# SecurityLock.net
KiCad netlist of a schematic drawn in Altium Designer
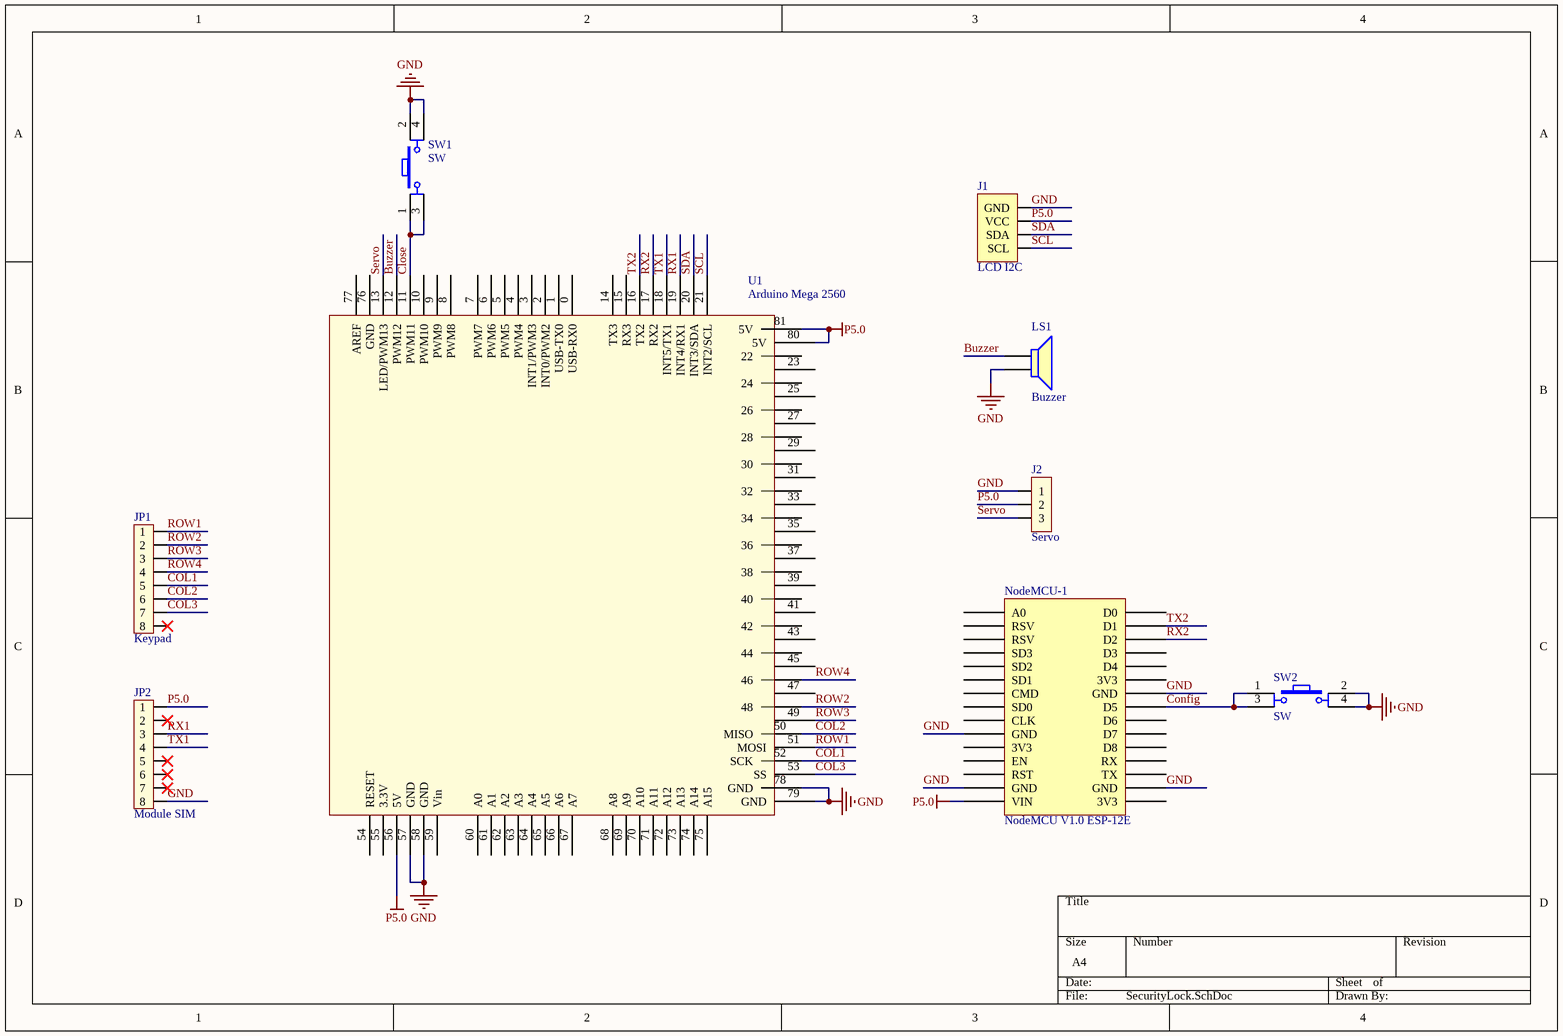
[diagram p0: SecurityLock.SchDoc]

(export (version "E")
  (design (tool "Eeschema 10.0.6"))
  (components
    (comp (ref "J1") (value "LCD I2C") (footprint "LCD16x2_I2C") (libsource (lib "jmctvs") (part "LCD I2C")))
    (comp (ref "J2")
      (value "Servo")
      (footprint "JP3")
      (description "Jumper 3")
      (libsource (lib "jmctvs") (part "JP3"))
    )
    (comp (ref "JP1")
      (value "Keypad")
      (footprint "JP8")
      (description "JP8 PIN")
      (libsource (lib "jmctvs") (part "JP8"))
    )
    (comp (ref "JP2")
      (value "Module SIM")
      (footprint "JP8")
      (description "JP8 PIN")
      (libsource (lib "jmctvs") (part "JP8"))
    )
    (comp (ref "LS1")
      (value "Buzzer")
      (footprint "Buzzer")
      (description "Magnetic Transducer Buzzer")
      (fields (field (name "DESIGNED BY") "John MacTavish"))
      (libsource (lib "jmctvs") (part "Buzzer"))
    )
    (comp (ref "NodeMCU-1")
      (value "NodeMCU V1.0 ESP-12E")
      (footprint "jmctvs:NodeMCU V1.0 ESP-12E")
      (description "NodeMCU V1.0 ESP8266 (ESP-12E)")
      (libsource (lib "jmctvs") (part "NodeMCU V1.0 ESP-12E"))
    )
    (comp (ref "SW1")
      (value "SW")
      (footprint "SW4")
      (description "Switch button 4 pin")
      (libsource (lib "jmctvs") (part "SW4"))
    )
    (comp (ref "SW2")
      (value "SW")
      (footprint "SW4")
      (description "Switch button 4 pin")
      (libsource (lib "") (part "SW4_1"))
    )
    (comp (ref "U1")
      (value "Arduino Mega 2560")
      (footprint "Arduino System:Arduino")
      (libsource (lib "jmctvs") (part "Arduino Mega 2560"))
    )
  )
  (nets
    (net (code "1") (name "/Buzzer") (class "Default")
      (node (ref "LS1") (pin "1") (pinfunction "1_1") (pintype "passive"))
      (node (ref "U1") (pin "12") (pinfunction "PWM12_12") (pintype "passive"))
    )
    (net (code "2") (name "/COL1") (class "Default")
      (node (ref "JP1") (pin "5") (pinfunction "5_5") (pintype "passive"))
      (node (ref "U1") (pin "52") (pinfunction "SCK_52") (pintype "passive"))
    )
    (net (code "3") (name "/COL2") (class "Default")
      (node (ref "JP1") (pin "6") (pinfunction "6_6") (pintype "passive"))
      (node (ref "U1") (pin "50") (pinfunction "MISO_50") (pintype "passive"))
    )
    (net (code "4") (name "/COL3") (class "Default")
      (node (ref "JP1") (pin "7") (pinfunction "7_7") (pintype "passive"))
      (node (ref "U1") (pin "53") (pinfunction "SS_53") (pintype "passive"))
    )
    (net (code "5") (name "/Close") (class "Default")
      (node (ref "SW1") (pin "1") (pintype "passive"))
      (node (ref "SW1") (pin "3") (pintype "passive"))
      (node (ref "U1") (pin "11") (pinfunction "PWM11_11") (pintype "passive"))
    )
    (net (code "6") (name "/Config") (class "Default")
      (node (ref "NodeMCU-1") (pin "D5") (pinfunction "D5_D5") (pintype "passive"))
      (node (ref "SW2") (pin "1") (pintype "passive"))
      (node (ref "SW2") (pin "3") (pintype "passive"))
    )
    (net (code "7") (name "/ROW1") (class "Default")
      (node (ref "JP1") (pin "1") (pinfunction "1_1") (pintype "passive"))
      (node (ref "U1") (pin "51") (pinfunction "MOSI_51") (pintype "passive"))
    )
    (net (code "8") (name "/ROW2") (class "Default")
      (node (ref "JP1") (pin "2") (pinfunction "2_2") (pintype "passive"))
      (node (ref "U1") (pin "48") (pinfunction "48_48") (pintype "passive"))
    )
    (net (code "9") (name "/ROW3") (class "Default")
      (node (ref "JP1") (pin "3") (pinfunction "3_3") (pintype "passive"))
      (node (ref "U1") (pin "49") (pinfunction "49_49") (pintype "passive"))
    )
    (net (code "10") (name "/ROW4") (class "Default")
      (node (ref "JP1") (pin "4") (pinfunction "4_4") (pintype "passive"))
      (node (ref "U1") (pin "46") (pinfunction "46_46") (pintype "passive"))
    )
    (net (code "11") (name "/RX1") (class "Default")
      (node (ref "JP2") (pin "3") (pinfunction "3_3") (pintype "passive"))
      (node (ref "U1") (pin "19") (pinfunction "INT4/RX1_19") (pintype "passive"))
    )
    (net (code "12") (name "/RX2") (class "Default")
      (node (ref "NodeMCU-1") (pin "D2") (pinfunction "D2_D2") (pintype "passive"))
      (node (ref "U1") (pin "17") (pinfunction "RX2_17") (pintype "passive"))
    )
    (net (code "13") (name "/SCL") (class "Default")
      (node (ref "J1") (pin "4") (pinfunction "SCL_4") (pintype "passive"))
      (node (ref "U1") (pin "21") (pinfunction "INT2/SCL_21") (pintype "passive"))
    )
    (net (code "14") (name "/SDA") (class "Default")
      (node (ref "J1") (pin "3") (pinfunction "SDA_3") (pintype "passive"))
      (node (ref "U1") (pin "20") (pinfunction "INT3/SDA_20") (pintype "passive"))
    )
    (net (code "15") (name "/Servo") (class "Default")
      (node (ref "J2") (pin "3") (pinfunction "3_3") (pintype "passive"))
      (node (ref "U1") (pin "13") (pinfunction "LED/PWM13_13") (pintype "passive"))
    )
    (net (code "16") (name "/TX1") (class "Default")
      (node (ref "JP2") (pin "4") (pinfunction "4_4") (pintype "passive"))
      (node (ref "U1") (pin "18") (pinfunction "INT5/TX1_18") (pintype "passive"))
    )
    (net (code "17") (name "/TX2") (class "Default")
      (node (ref "NodeMCU-1") (pin "D1") (pinfunction "D1_D1") (pintype "passive"))
      (node (ref "U1") (pin "16") (pinfunction "TX2_16") (pintype "passive"))
    )
    (net (code "18") (name "GND") (class "Default")
      (node (ref "J1") (pin "1") (pinfunction "GND_1") (pintype "passive"))
      (node (ref "J2") (pin "1") (pinfunction "1_1") (pintype "passive"))
      (node (ref "JP2") (pin "8") (pinfunction "8_8") (pintype "passive"))
      (node (ref "LS1") (pin "2") (pinfunction "2_2") (pintype "passive"))
      (node (ref "NodeMCU-1") (pin "GND") (pinfunction "GND_GND") (pintype "passive"))
      (node (ref "SW1") (pin "2") (pintype "passive"))
      (node (ref "SW1") (pin "4") (pintype "passive"))
      (node (ref "SW2") (pin "2") (pintype "passive"))
      (node (ref "SW2") (pin "4") (pintype "passive"))
      (node (ref "U1") (pin "57") (pinfunction "GND_57") (pintype "passive"))
      (node (ref "U1") (pin "58") (pinfunction "GND_58") (pintype "passive"))
      (node (ref "U1") (pin "78") (pinfunction "GND_78") (pintype "passive"))
      (node (ref "U1") (pin "79") (pinfunction "GND_79") (pintype "passive"))
    )
    (net (code "19") (name "P5.0") (class "Default")
      (node (ref "J1") (pin "2") (pinfunction "VCC_2") (pintype "passive"))
      (node (ref "J2") (pin "2") (pinfunction "2_2") (pintype "passive"))
      (node (ref "JP2") (pin "1") (pinfunction "1_1") (pintype "passive"))
      (node (ref "NodeMCU-1") (pin "VIN") (pinfunction "VIN_VIN") (pintype "passive"))
      (node (ref "U1") (pin "56") (pinfunction "5V_56") (pintype "passive"))
      (node (ref "U1") (pin "80") (pinfunction "5V_80") (pintype "passive"))
      (node (ref "U1") (pin "81") (pinfunction "5V_81") (pintype "passive"))
    )
    (net (code "20") (name "unconnected-(JP1-Pad8)") (class "Default")
      (node (ref "JP1") (pin "8") (pinfunction "8_8") (pintype "passive+no_connect"))
    )
    (net (code "21") (name "unconnected-(JP2-Pad2)") (class "Default")
      (node (ref "JP2") (pin "2") (pinfunction "2_2") (pintype "passive+no_connect"))
    )
    (net (code "22") (name "unconnected-(JP2-Pad5)") (class "Default")
      (node (ref "JP2") (pin "5") (pinfunction "5_5") (pintype "passive+no_connect"))
    )
    (net (code "23") (name "unconnected-(JP2-Pad6)") (class "Default")
      (node (ref "JP2") (pin "6") (pinfunction "6_6") (pintype "passive+no_connect"))
    )
    (net (code "24") (name "unconnected-(JP2-Pad7)") (class "Default")
      (node (ref "JP2") (pin "7") (pinfunction "7_7") (pintype "passive+no_connect"))
    )
    (net (code "25") (name "unconnected-(NodeMCU-1-Pad3V3)") (class "Default")
      (node (ref "NodeMCU-1") (pin "3V3") (pinfunction "3V3_3V3") (pintype "passive"))
    )
    (net (code "26") (name "unconnected-(NodeMCU-1-Pad3V3)_1") (class "Default")
      (node (ref "NodeMCU-1") (pin "3V3") (pinfunction "3V3_3V3") (pintype "passive"))
    )
    (net (code "27") (name "unconnected-(NodeMCU-1-Pad3V3)_2") (class "Default")
      (node (ref "NodeMCU-1") (pin "3V3") (pinfunction "3V3_3V3") (pintype "passive"))
    )
    (net (code "28") (name "unconnected-(NodeMCU-1-PadA0)") (class "Default")
      (node (ref "NodeMCU-1") (pin "A0") (pinfunction "A0_A0") (pintype "passive"))
    )
    (net (code "29") (name "unconnected-(NodeMCU-1-PadCLK)") (class "Default")
      (node (ref "NodeMCU-1") (pin "CLK") (pinfunction "CLK_CLK") (pintype "passive"))
    )
    (net (code "30") (name "unconnected-(NodeMCU-1-PadCMD)") (class "Default")
      (node (ref "NodeMCU-1") (pin "CMD") (pinfunction "CMD_CMD") (pintype "passive"))
    )
    (net (code "31") (name "unconnected-(NodeMCU-1-PadD0)") (class "Default")
      (node (ref "NodeMCU-1") (pin "D0") (pinfunction "D0_D0") (pintype "passive"))
    )
    (net (code "32") (name "unconnected-(NodeMCU-1-PadD3)") (class "Default")
      (node (ref "NodeMCU-1") (pin "D3") (pinfunction "D3_D3") (pintype "passive"))
    )
    (net (code "33") (name "unconnected-(NodeMCU-1-PadD4)") (class "Default")
      (node (ref "NodeMCU-1") (pin "D4") (pinfunction "D4_D4") (pintype "passive"))
    )
    (net (code "34") (name "unconnected-(NodeMCU-1-PadD6)") (class "Default")
      (node (ref "NodeMCU-1") (pin "D6") (pinfunction "D6_D6") (pintype "passive"))
    )
    (net (code "35") (name "unconnected-(NodeMCU-1-PadD7)") (class "Default")
      (node (ref "NodeMCU-1") (pin "D7") (pinfunction "D7_D7") (pintype "passive"))
    )
    (net (code "36") (name "unconnected-(NodeMCU-1-PadD8)") (class "Default")
      (node (ref "NodeMCU-1") (pin "D8") (pinfunction "D8_D8") (pintype "passive"))
    )
    (net (code "37") (name "unconnected-(NodeMCU-1-PadEN)") (class "Default")
      (node (ref "NodeMCU-1") (pin "EN") (pinfunction "EN_EN") (pintype "passive"))
    )
    (net (code "38") (name "unconnected-(NodeMCU-1-PadRST)") (class "Default")
      (node (ref "NodeMCU-1") (pin "RST") (pinfunction "RST_RST") (pintype "passive"))
    )
    (net (code "39") (name "unconnected-(NodeMCU-1-PadRSV)") (class "Default")
      (node (ref "NodeMCU-1") (pin "RSV") (pinfunction "RSV_RSV") (pintype "passive"))
    )
    (net (code "40") (name "unconnected-(NodeMCU-1-PadRSV)_1") (class "Default")
      (node (ref "NodeMCU-1") (pin "RSV") (pinfunction "RSV_RSV") (pintype "passive"))
    )
    (net (code "41") (name "unconnected-(NodeMCU-1-PadRX)") (class "Default")
      (node (ref "NodeMCU-1") (pin "RX") (pinfunction "RX_RX") (pintype "passive"))
    )
    (net (code "42") (name "unconnected-(NodeMCU-1-PadSD0)") (class "Default")
      (node (ref "NodeMCU-1") (pin "SD0") (pinfunction "SD0_SD0") (pintype "passive"))
    )
    (net (code "43") (name "unconnected-(NodeMCU-1-PadSD1)") (class "Default")
      (node (ref "NodeMCU-1") (pin "SD1") (pinfunction "SD1_SD1") (pintype "passive"))
    )
    (net (code "44") (name "unconnected-(NodeMCU-1-PadSD2)") (class "Default")
      (node (ref "NodeMCU-1") (pin "SD2") (pinfunction "SD2_SD2") (pintype "passive"))
    )
    (net (code "45") (name "unconnected-(NodeMCU-1-PadSD3)") (class "Default")
      (node (ref "NodeMCU-1") (pin "SD3") (pinfunction "SD3_SD3") (pintype "passive"))
    )
    (net (code "46") (name "unconnected-(NodeMCU-1-PadTX)") (class "Default")
      (node (ref "NodeMCU-1") (pin "TX") (pinfunction "TX_TX") (pintype "passive"))
    )
    (net (code "47") (name "unconnected-(U1-3.3V-Pad55)") (class "Default")
      (node (ref "U1") (pin "55") (pinfunction "3.3V_55") (pintype "passive"))
    )
    (net (code "48") (name "unconnected-(U1-A0-Pad60)") (class "Default")
      (node (ref "U1") (pin "60") (pinfunction "A0_60") (pintype "passive"))
    )
    (net (code "49") (name "unconnected-(U1-A1-Pad61)") (class "Default")
      (node (ref "U1") (pin "61") (pinfunction "A1_61") (pintype "passive"))
    )
    (net (code "50") (name "unconnected-(U1-A2-Pad62)") (class "Default")
      (node (ref "U1") (pin "62") (pinfunction "A2_62") (pintype "passive"))
    )
    (net (code "51") (name "unconnected-(U1-A3-Pad63)") (class "Default")
      (node (ref "U1") (pin "63") (pinfunction "A3_63") (pintype "passive"))
    )
    (net (code "52") (name "unconnected-(U1-A4-Pad64)") (class "Default")
      (node (ref "U1") (pin "64") (pinfunction "A4_64") (pintype "passive"))
    )
    (net (code "53") (name "unconnected-(U1-A5-Pad65)") (class "Default")
      (node (ref "U1") (pin "65") (pinfunction "A5_65") (pintype "passive"))
    )
    (net (code "54") (name "unconnected-(U1-A6-Pad66)") (class "Default")
      (node (ref "U1") (pin "66") (pinfunction "A6_66") (pintype "passive"))
    )
    (net (code "55") (name "unconnected-(U1-A7-Pad67)") (class "Default")
      (node (ref "U1") (pin "67") (pinfunction "A7_67") (pintype "passive"))
    )
    (net (code "56") (name "unconnected-(U1-A8-Pad68)") (class "Default")
      (node (ref "U1") (pin "68") (pinfunction "A8_68") (pintype "passive"))
    )
    (net (code "57") (name "unconnected-(U1-A9-Pad69)") (class "Default")
      (node (ref "U1") (pin "69") (pinfunction "A9_69") (pintype "passive"))
    )
    (net (code "58") (name "unconnected-(U1-A10-Pad70)") (class "Default")
      (node (ref "U1") (pin "70") (pinfunction "A10_70") (pintype "passive"))
    )
    (net (code "59") (name "unconnected-(U1-A11-Pad71)") (class "Default")
      (node (ref "U1") (pin "71") (pinfunction "A11_71") (pintype "passive"))
    )
    (net (code "60") (name "unconnected-(U1-A12-Pad72)") (class "Default")
      (node (ref "U1") (pin "72") (pinfunction "A12_72") (pintype "passive"))
    )
    (net (code "61") (name "unconnected-(U1-A13-Pad73)") (class "Default")
      (node (ref "U1") (pin "73") (pinfunction "A13_73") (pintype "passive"))
    )
    (net (code "62") (name "unconnected-(U1-A14-Pad74)") (class "Default")
      (node (ref "U1") (pin "74") (pinfunction "A14_74") (pintype "passive"))
    )
    (net (code "63") (name "unconnected-(U1-A15-Pad75)") (class "Default")
      (node (ref "U1") (pin "75") (pinfunction "A15_75") (pintype "passive"))
    )
    (net (code "64") (name "unconnected-(U1-AREF-Pad77)") (class "Default")
      (node (ref "U1") (pin "77") (pinfunction "AREF_77") (pintype "passive"))
    )
    (net (code "65") (name "unconnected-(U1-GND-Pad76)") (class "Default")
      (node (ref "U1") (pin "76") (pinfunction "GND_76") (pintype "passive"))
    )
    (net (code "66") (name "unconnected-(U1-INT0{slash}PWM2-Pad2)") (class "Default")
      (node (ref "U1") (pin "2") (pinfunction "INT0/PWM2_2") (pintype "passive"))
    )
    (net (code "67") (name "unconnected-(U1-INT1{slash}PWM3-Pad3)") (class "Default")
      (node (ref "U1") (pin "3") (pinfunction "INT1/PWM3_3") (pintype "passive"))
    )
    (net (code "68") (name "unconnected-(U1-PWM4-Pad4)") (class "Default")
      (node (ref "U1") (pin "4") (pinfunction "PWM4_4") (pintype "passive"))
    )
    (net (code "69") (name "unconnected-(U1-PWM5-Pad5)") (class "Default")
      (node (ref "U1") (pin "5") (pinfunction "PWM5_5") (pintype "passive"))
    )
    (net (code "70") (name "unconnected-(U1-PWM6-Pad6)") (class "Default")
      (node (ref "U1") (pin "6") (pinfunction "PWM6_6") (pintype "passive"))
    )
    (net (code "71") (name "unconnected-(U1-PWM7-Pad7)") (class "Default")
      (node (ref "U1") (pin "7") (pinfunction "PWM7_7") (pintype "passive"))
    )
    (net (code "72") (name "unconnected-(U1-PWM8-Pad8)") (class "Default")
      (node (ref "U1") (pin "8") (pinfunction "PWM8_8") (pintype "passive"))
    )
    (net (code "73") (name "unconnected-(U1-PWM9-Pad9)") (class "Default")
      (node (ref "U1") (pin "9") (pinfunction "PWM9_9") (pintype "passive"))
    )
    (net (code "74") (name "unconnected-(U1-PWM10-Pad10)") (class "Default")
      (node (ref "U1") (pin "10") (pinfunction "PWM10_10") (pintype "passive"))
    )
    (net (code "75") (name "unconnected-(U1-Pad22)") (class "Default")
      (node (ref "U1") (pin "22") (pinfunction "22_22") (pintype "passive"))
    )
    (net (code "76") (name "unconnected-(U1-Pad23)") (class "Default")
      (node (ref "U1") (pin "23") (pinfunction "23_23") (pintype "passive"))
    )
    (net (code "77") (name "unconnected-(U1-Pad24)") (class "Default")
      (node (ref "U1") (pin "24") (pinfunction "24_24") (pintype "passive"))
    )
    (net (code "78") (name "unconnected-(U1-Pad25)") (class "Default")
      (node (ref "U1") (pin "25") (pinfunction "25_25") (pintype "passive"))
    )
    (net (code "79") (name "unconnected-(U1-Pad26)") (class "Default")
      (node (ref "U1") (pin "26") (pinfunction "26_26") (pintype "passive"))
    )
    (net (code "80") (name "unconnected-(U1-Pad27)") (class "Default")
      (node (ref "U1") (pin "27") (pinfunction "27_27") (pintype "passive"))
    )
    (net (code "81") (name "unconnected-(U1-Pad28)") (class "Default")
      (node (ref "U1") (pin "28") (pinfunction "28_28") (pintype "passive"))
    )
    (net (code "82") (name "unconnected-(U1-Pad29)") (class "Default")
      (node (ref "U1") (pin "29") (pinfunction "29_29") (pintype "passive"))
    )
    (net (code "83") (name "unconnected-(U1-Pad30)") (class "Default")
      (node (ref "U1") (pin "30") (pinfunction "30_30") (pintype "passive"))
    )
    (net (code "84") (name "unconnected-(U1-Pad31)") (class "Default")
      (node (ref "U1") (pin "31") (pinfunction "31_31") (pintype "passive"))
    )
    (net (code "85") (name "unconnected-(U1-Pad32)") (class "Default")
      (node (ref "U1") (pin "32") (pinfunction "32_32") (pintype "passive"))
    )
    (net (code "86") (name "unconnected-(U1-Pad33)") (class "Default")
      (node (ref "U1") (pin "33") (pinfunction "33_33") (pintype "passive"))
    )
    (net (code "87") (name "unconnected-(U1-Pad34)") (class "Default")
      (node (ref "U1") (pin "34") (pinfunction "34_34") (pintype "passive"))
    )
    (net (code "88") (name "unconnected-(U1-Pad35)") (class "Default")
      (node (ref "U1") (pin "35") (pinfunction "35_35") (pintype "passive"))
    )
    (net (code "89") (name "unconnected-(U1-Pad36)") (class "Default")
      (node (ref "U1") (pin "36") (pinfunction "36_36") (pintype "passive"))
    )
    (net (code "90") (name "unconnected-(U1-Pad37)") (class "Default")
      (node (ref "U1") (pin "37") (pinfunction "37_37") (pintype "passive"))
    )
    (net (code "91") (name "unconnected-(U1-Pad38)") (class "Default")
      (node (ref "U1") (pin "38") (pinfunction "38_38") (pintype "passive"))
    )
    (net (code "92") (name "unconnected-(U1-Pad39)") (class "Default")
      (node (ref "U1") (pin "39") (pinfunction "39_39") (pintype "passive"))
    )
    (net (code "93") (name "unconnected-(U1-Pad40)") (class "Default")
      (node (ref "U1") (pin "40") (pinfunction "40_40") (pintype "passive"))
    )
    (net (code "94") (name "unconnected-(U1-Pad41)") (class "Default")
      (node (ref "U1") (pin "41") (pinfunction "41_41") (pintype "passive"))
    )
    (net (code "95") (name "unconnected-(U1-Pad42)") (class "Default")
      (node (ref "U1") (pin "42") (pinfunction "42_42") (pintype "passive"))
    )
    (net (code "96") (name "unconnected-(U1-Pad43)") (class "Default")
      (node (ref "U1") (pin "43") (pinfunction "43_43") (pintype "passive"))
    )
    (net (code "97") (name "unconnected-(U1-Pad44)") (class "Default")
      (node (ref "U1") (pin "44") (pinfunction "44_44") (pintype "passive"))
    )
    (net (code "98") (name "unconnected-(U1-Pad45)") (class "Default")
      (node (ref "U1") (pin "45") (pinfunction "45_45") (pintype "passive"))
    )
    (net (code "99") (name "unconnected-(U1-Pad47)") (class "Default")
      (node (ref "U1") (pin "47") (pinfunction "47_47") (pintype "passive"))
    )
    (net (code "100") (name "unconnected-(U1-RESET-Pad54)") (class "Default")
      (node (ref "U1") (pin "54") (pinfunction "RESET_54") (pintype "passive"))
    )
    (net (code "101") (name "unconnected-(U1-RX3-Pad15)") (class "Default")
      (node (ref "U1") (pin "15") (pinfunction "RX3_15") (pintype "passive"))
    )
    (net (code "102") (name "unconnected-(U1-TX3-Pad14)") (class "Default")
      (node (ref "U1") (pin "14") (pinfunction "TX3_14") (pintype "passive"))
    )
    (net (code "103") (name "unconnected-(U1-USB-RX0-Pad0)") (class "Default")
      (node (ref "U1") (pin "0") (pinfunction "USB-RX0_0") (pintype "passive"))
    )
    (net (code "104") (name "unconnected-(U1-USB-TX0-Pad1)") (class "Default")
      (node (ref "U1") (pin "1") (pinfunction "USB-TX0_1") (pintype "passive"))
    )
    (net (code "105") (name "unconnected-(U1-Vin-Pad59)") (class "Default")
      (node (ref "U1") (pin "59") (pinfunction "Vin_59") (pintype "passive"))
    )
  )
)
